# Oled128x32.net
KiCad netlist of a schematic drawn in EAGLE
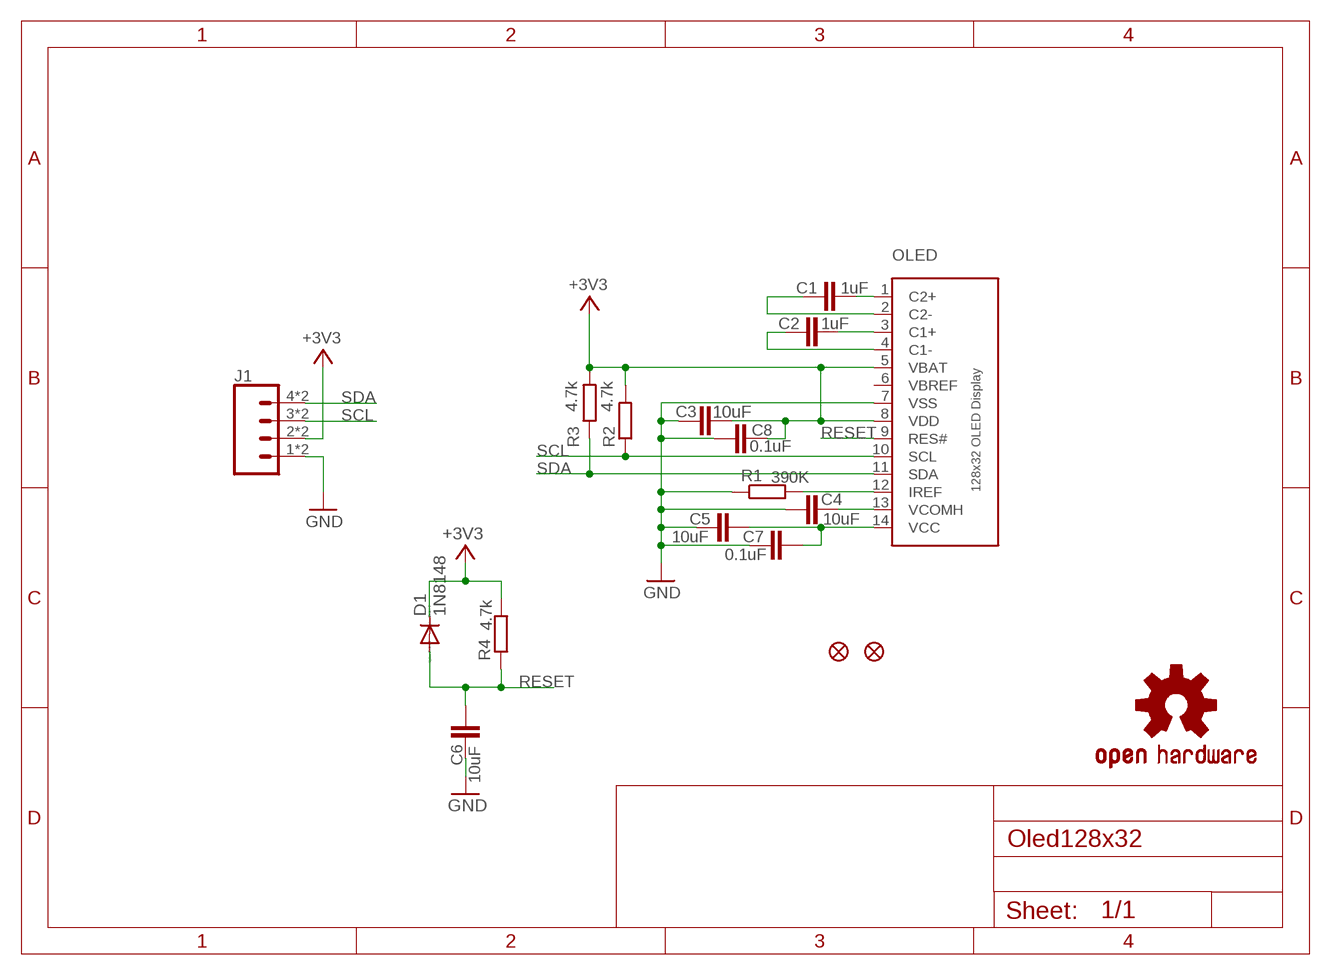
[diagram p0: schematic, sheet 1]

(export (version "E")
  (design (tool "Eeschema 10.0.6"))
  (components
    (comp (ref "C1")
      (value "1uF")
      (footprint "eagle-import:C0603")
      (libsource (lib "eagle-import") (part "C-EUC0603"))
    )
    (comp (ref "C2")
      (value "1uF")
      (footprint "eagle-import:C0603")
      (libsource (lib "eagle-import") (part "C-EUC0603"))
    )
    (comp (ref "C3")
      (value "10uF")
      (footprint "eagle-import:C0603")
      (libsource (lib "eagle-import") (part "C-EUC0603"))
    )
    (comp (ref "C4")
      (value "10uF")
      (footprint "eagle-import:C0603")
      (libsource (lib "eagle-import") (part "C-EUC0603"))
    )
    (comp (ref "C5")
      (value "10uF")
      (footprint "eagle-import:C0603")
      (libsource (lib "eagle-import") (part "C-EUC0603"))
    )
    (comp (ref "C6")
      (value "10uF")
      (footprint "eagle-import:C0603")
      (libsource (lib "eagle-import") (part "C-EUC0603"))
    )
    (comp (ref "C7")
      (value "0.1uF")
      (footprint "eagle-import:C0603")
      (libsource (lib "eagle-import") (part "C-EUC0603"))
    )
    (comp (ref "C8")
      (value "0.1uF")
      (footprint "eagle-import:C0603")
      (libsource (lib "eagle-import") (part "C-EUC0603"))
    )
    (comp (ref "D1")
      (value "1N8148")
      (footprint "eagle-import:SOD110-W")
      (libsource (lib "eagle-import") (part "DIODE-SOD110-W"))
    )
    (comp (ref "FD1")
      (value "FIDUCIAL1X2")
      (footprint "eagle-import:FIDUCIAL-1X2")
      (libsource (lib "eagle-import") (part "FIDUCIAL1X2"))
    )
    (comp (ref "FD2")
      (value "FIDUCIAL1X2")
      (footprint "eagle-import:FIDUCIAL-1X2")
      (libsource (lib "eagle-import") (part "FIDUCIAL1X2"))
    )
    (comp (ref "J1")
      (value "1X04_SMD_STRAIGHT_COMBO")
      (footprint "eagle-import:1X04_SMD_VERTICAL_COMBO")
      (libsource (lib "eagle-import") (part "CONN_04SMD_STRAIGHT_COMBO"))
    )
    (comp (ref "LOGO1")
      (value "OSHW-LOGOS")
      (footprint "eagle-import:OSHW-LOGO-S")
      (libsource (lib "eagle-import") (part "OSHW-LOGOS"))
    )
    (comp (ref "OLED")
      (value "OLED_128X32_UG-2832HSWEG02")
      (footprint "eagle-import:OLED_128X32_UG-2832HSWEG02_WRAPUNDER")
      (libsource (lib "eagle-import") (part "OLED_128X32_UG-2832HSWEG02"))
    )
    (comp (ref "R1")
      (value "390K")
      (footprint "eagle-import:R0603")
      (libsource (lib "eagle-import") (part "R-EU_R0603"))
    )
    (comp (ref "R2")
      (value "4.7k")
      (footprint "eagle-import:R0603")
      (libsource (lib "eagle-import") (part "R-EU_R0603"))
    )
    (comp (ref "R3")
      (value "4.7k")
      (footprint "eagle-import:R0603")
      (libsource (lib "eagle-import") (part "R-EU_R0603"))
    )
    (comp (ref "R4")
      (value "4.7k")
      (footprint "eagle-import:R0603")
      (libsource (lib "eagle-import") (part "R-EU_R0603"))
    )
  )
  (nets
    (net (code "1") (name "+3V3") (class "Default")
      (node (ref "C3") (pin "2") (pinfunction "2_2") (pintype "passive"))
      (node (ref "C8") (pin "2") (pinfunction "2_2") (pintype "passive"))
      (node (ref "D1") (pin "C") (pinfunction "C_C") (pintype "passive"))
      (node (ref "J1") (pin "2") (pinfunction "2_2") (pintype "passive"))
      (node (ref "J1") (pin "2-2") (pinfunction "2_2-2") (pintype "passive"))
      (node (ref "OLED") (pin "5") (pinfunction "VBAT_5") (pintype "power_in"))
      (node (ref "OLED") (pin "8") (pinfunction "VDD_8") (pintype "power_in"))
      (node (ref "R2") (pin "2") (pinfunction "2_2") (pintype "passive"))
      (node (ref "R3") (pin "2") (pinfunction "2_2") (pintype "passive"))
      (node (ref "R4") (pin "2") (pinfunction "2_2") (pintype "passive"))
    )
    (net (code "2") (name "/RESET") (class "Default")
      (node (ref "C6") (pin "2") (pinfunction "2_2") (pintype "passive"))
      (node (ref "D1") (pin "A") (pinfunction "A_A") (pintype "passive"))
      (node (ref "OLED") (pin "9") (pinfunction "RES#_9") (pintype "bidirectional"))
      (node (ref "R4") (pin "1") (pinfunction "1_1") (pintype "passive"))
    )
    (net (code "3") (name "/SCL") (class "Default")
      (node (ref "J1") (pin "3") (pinfunction "3_3") (pintype "passive"))
      (node (ref "J1") (pin "3-2") (pinfunction "3_3-2") (pintype "passive"))
      (node (ref "OLED") (pin "10") (pinfunction "SCL_10") (pintype "bidirectional"))
      (node (ref "R2") (pin "1") (pinfunction "1_1") (pintype "passive"))
    )
    (net (code "4") (name "/SDA") (class "Default")
      (node (ref "J1") (pin "4") (pinfunction "4_4") (pintype "passive"))
      (node (ref "J1") (pin "4-2") (pinfunction "4_4-2") (pintype "passive"))
      (node (ref "OLED") (pin "11") (pinfunction "SDA_11") (pintype "bidirectional"))
      (node (ref "R3") (pin "1") (pinfunction "1_1") (pintype "passive"))
    )
    (net (code "5") (name "/VBREF") (class "Default")
      (node (ref "OLED") (pin "6") (pinfunction "VBREF_6") (pintype "power_in"))
    )
    (net (code "6") (name "GND") (class "Default")
      (node (ref "C3") (pin "1") (pinfunction "1_1") (pintype "passive"))
      (node (ref "C4") (pin "1") (pinfunction "1_1") (pintype "passive"))
      (node (ref "C5") (pin "1") (pinfunction "1_1") (pintype "passive"))
      (node (ref "C6") (pin "1") (pinfunction "1_1") (pintype "passive"))
      (node (ref "C7") (pin "1") (pinfunction "1_1") (pintype "passive"))
      (node (ref "C8") (pin "1") (pinfunction "1_1") (pintype "passive"))
      (node (ref "J1") (pin "1") (pinfunction "1_1") (pintype "passive"))
      (node (ref "J1") (pin "1-2") (pinfunction "1_1-2") (pintype "passive"))
      (node (ref "OLED") (pin "7") (pinfunction "VSS_7") (pintype "power_in"))
      (node (ref "R1") (pin "1") (pinfunction "1_1") (pintype "passive"))
    )
    (net (code "7") (name "Net-(OLED-C1+)") (class "Default")
      (node (ref "C2") (pin "2") (pinfunction "2_2") (pintype "passive"))
      (node (ref "OLED") (pin "3") (pinfunction "C1+_3") (pintype "bidirectional"))
    )
    (net (code "8") (name "Net-(OLED-C1-)") (class "Default")
      (node (ref "C2") (pin "1") (pinfunction "1_1") (pintype "passive"))
      (node (ref "OLED") (pin "4") (pinfunction "C1-_4") (pintype "bidirectional"))
    )
    (net (code "9") (name "Net-(OLED-C2+)") (class "Default")
      (node (ref "C1") (pin "2") (pinfunction "2_2") (pintype "passive"))
      (node (ref "OLED") (pin "1") (pinfunction "C2+_1") (pintype "bidirectional"))
    )
    (net (code "10") (name "Net-(OLED-C2-)") (class "Default")
      (node (ref "C1") (pin "1") (pinfunction "1_1") (pintype "passive"))
      (node (ref "OLED") (pin "2") (pinfunction "C2-_2") (pintype "bidirectional"))
    )
    (net (code "11") (name "Net-(OLED-IREF)") (class "Default")
      (node (ref "OLED") (pin "12") (pinfunction "IREF_12") (pintype "bidirectional"))
      (node (ref "R1") (pin "2") (pinfunction "2_2") (pintype "passive"))
    )
    (net (code "12") (name "Net-(OLED-VCC)") (class "Default")
      (node (ref "C5") (pin "2") (pinfunction "2_2") (pintype "passive"))
      (node (ref "C7") (pin "2") (pinfunction "2_2") (pintype "passive"))
      (node (ref "OLED") (pin "14") (pinfunction "VCC_14") (pintype "power_in"))
    )
    (net (code "13") (name "Net-(OLED-VCOMH)") (class "Default")
      (node (ref "C4") (pin "2") (pinfunction "2_2") (pintype "passive"))
      (node (ref "OLED") (pin "13") (pinfunction "VCOMH_13") (pintype "power_in"))
    )
  )
)
